# blinky_tag_tht_ver1.net
KiCad netlist of a schematic drawn in EAGLE
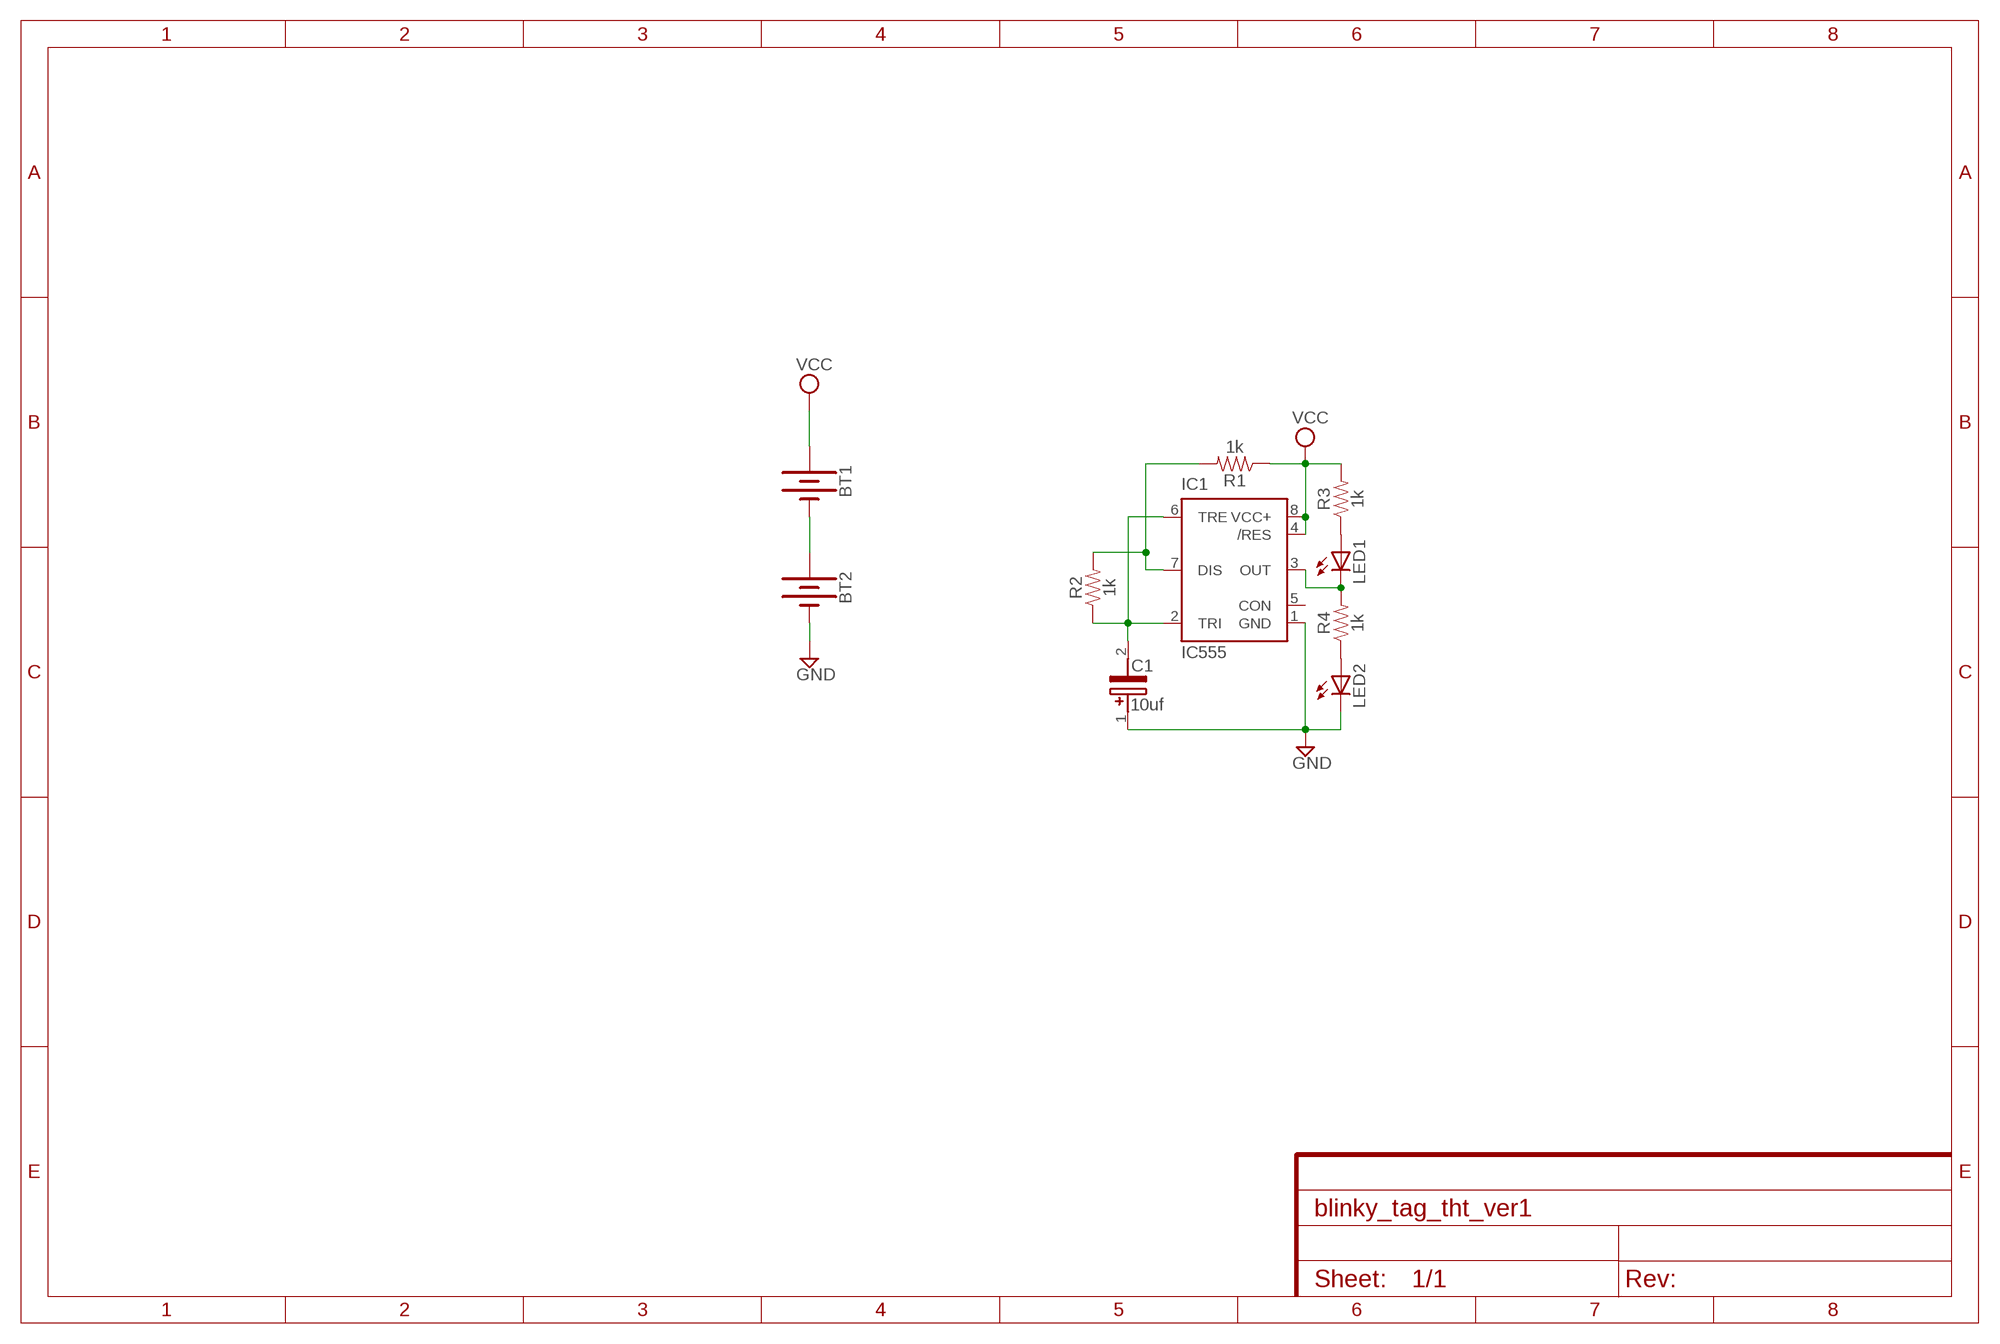
[diagram p0: schematic, sheet 1]

(export (version "E")
  (design (tool "Eeschema 10.0.6"))
  (components
    (comp (ref "BT1")
      (value "BATTERY-12MM_SMD")
      (footprint "eagle-import:BATTCON_12MM")
      (libsource (lib "eagle-import") (part "BATTERY-12MM_SMD"))
    )
    (comp (ref "BT2")
      (value "BATTERY-12MM_SMD")
      (footprint "eagle-import:BATTCON_12MM")
      (libsource (lib "eagle-import") (part "BATTERY-12MM_SMD"))
    )
    (comp (ref "C1")
      (value "10uf")
      (footprint "eagle-import:CAPPRD200W52D500H1250")
      (fields
        (field (name "MANUFACTURER_PART_NUMBER") "860020472003")
        (field (name "MOUSER_PART_NUMBER") "710-860020472003")
        (field (name "RS_PART_NUMBER") "8396508P")
      )
      (libsource (lib "eagle-import") (part "860020472003"))
    )
    (comp (ref "IC1")
      (value "IC555")
      (footprint "eagle-import:DIP08-KIT")
      (fields (field (name "MF") "ON SEMICONDUCTOR") (field (name "MPN") "LM555CN"))
      (libsource (lib "eagle-import") (part "555KIT"))
    )
    (comp (ref "LED1")
      (value "LED5MM")
      (footprint "eagle-import:LED5MM")
      (libsource (lib "eagle-import") (part "LED5MM"))
    )
    (comp (ref "LED2")
      (value "LED5MM")
      (footprint "eagle-import:LED5MM")
      (libsource (lib "eagle-import") (part "LED5MM"))
    )
    (comp (ref "R1")
      (value "1k")
      (footprint "eagle-import:AXIAL-0.3")
      (libsource (lib "eagle-import") (part "1KOHM-HORIZ-1/4W-5%"))
    )
    (comp (ref "R2")
      (value "1k")
      (footprint "eagle-import:AXIAL-0.3")
      (libsource (lib "eagle-import") (part "1KOHM-HORIZ-1/4W-5%"))
    )
    (comp (ref "R3")
      (value "1k")
      (footprint "eagle-import:AXIAL-0.3")
      (libsource (lib "eagle-import") (part "1KOHM-HORIZ-1/4W-5%"))
    )
    (comp (ref "R4")
      (value "1k")
      (footprint "eagle-import:AXIAL-0.3")
      (libsource (lib "eagle-import") (part "1KOHM-HORIZ-1/4W-5%"))
    )
  )
  (nets
    (net (code "1") (name "GND") (class "Default")
      (node (ref "BT2") (pin "GND") (pinfunction "-_GND") (pintype "power_in"))
      (node (ref "C1") (pin "1") (pinfunction "+_1") (pintype "bidirectional"))
      (node (ref "IC1") (pin "1") (pinfunction "GND_1") (pintype "power_in"))
      (node (ref "LED2") (pin "K") (pinfunction "C_K") (pintype "passive"))
    )
    (net (code "2") (name "Net-(BT1--)") (class "Default")
      (node (ref "BT1") (pin "GND") (pinfunction "-_GND") (pintype "power_in"))
      (node (ref "BT2") (pin "PWR@1") (pinfunction "+_PWR@1") (pintype "power_in"))
    )
    (net (code "3") (name "Net-(C1--)") (class "Default")
      (node (ref "C1") (pin "2") (pinfunction "-_2") (pintype "bidirectional"))
      (node (ref "IC1") (pin "2") (pinfunction "TRI_2") (pintype "input"))
      (node (ref "IC1") (pin "6") (pinfunction "TRE_6") (pintype "input"))
      (node (ref "R2") (pin "P$1") (pinfunction "1_P$1") (pintype "passive"))
    )
    (net (code "4") (name "Net-(IC1-DIS)") (class "Default")
      (node (ref "IC1") (pin "7") (pinfunction "DIS_7") (pintype "input"))
      (node (ref "R1") (pin "P$2") (pinfunction "2_P$2") (pintype "passive"))
      (node (ref "R2") (pin "P$2") (pinfunction "2_P$2") (pintype "passive"))
    )
    (net (code "5") (name "Net-(IC1-OUT)") (class "Default")
      (node (ref "IC1") (pin "3") (pinfunction "OUT_3") (pintype "output"))
      (node (ref "LED1") (pin "K") (pinfunction "C_K") (pintype "passive"))
      (node (ref "R4") (pin "P$2") (pinfunction "2_P$2") (pintype "passive"))
    )
    (net (code "6") (name "Net-(R3-1)") (class "Default")
      (node (ref "LED1") (pin "A") (pinfunction "A_A") (pintype "passive"))
      (node (ref "R3") (pin "P$1") (pinfunction "1_P$1") (pintype "passive"))
    )
    (net (code "7") (name "Net-(R4-1)") (class "Default")
      (node (ref "LED2") (pin "A") (pinfunction "A_A") (pintype "passive"))
      (node (ref "R4") (pin "P$1") (pinfunction "1_P$1") (pintype "passive"))
    )
    (net (code "8") (name "VCC") (class "Default")
      (node (ref "BT1") (pin "PWR@1") (pinfunction "+_PWR@1") (pintype "power_in"))
      (node (ref "IC1") (pin "4") (pinfunction "/RES_4") (pintype "input"))
      (node (ref "IC1") (pin "8") (pinfunction "VCC+_8") (pintype "power_in"))
      (node (ref "R1") (pin "P$1") (pinfunction "1_P$1") (pintype "passive"))
      (node (ref "R3") (pin "P$2") (pinfunction "2_P$2") (pintype "passive"))
    )
    (net (code "9") (name "unconnected-(IC1-CON-Pad5)") (class "Default")
      (node (ref "IC1") (pin "5") (pinfunction "CON_5") (pintype "input"))
    )
  )
)
